# 03_-LED7SEG.net
KiCad netlist of a schematic drawn in Altium Designer
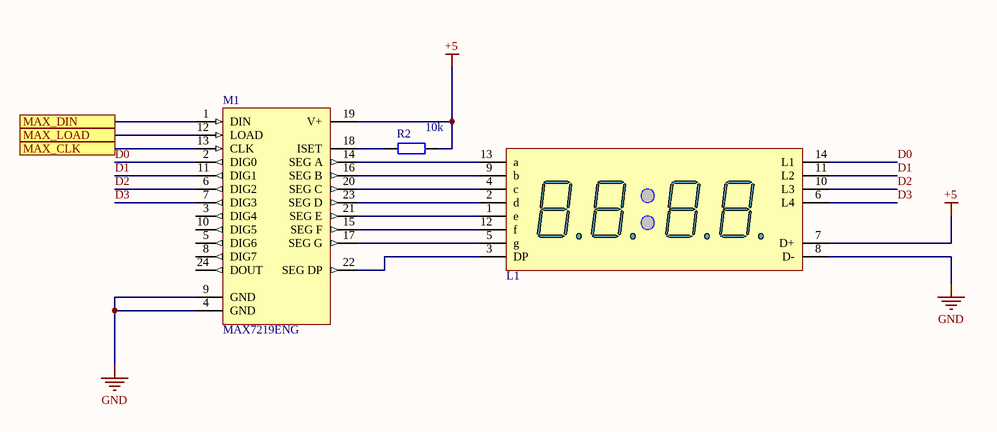
[diagram p0: [03]-LED7SEG.SchDoc]

(export (version "E")
  (design (tool "Eeschema 10.0.6"))
  (components
    (comp (ref "L1")
      (value "Led 7 Seg 4 digit - Anode")
      (footprint "LED7SEG-4-0.56-RG")
      (libsource (lib "My Library") (part "LED7SEG-4-RG"))
    )
    (comp (ref "M1")
      (value "MAX7219ENG")
      (footprint "DIP24/W0.3")
      (description "Serially Interfaced, 8-Digit LED Display Driver")
      (fields (field (name "PUBLISHER") "Altium Limited"))
      (libsource (lib "My Library") (part "MAX7219ENG"))
    )
    (comp (ref "R2")
      (value "10k")
      (footprint "RES_SMD_0805")
      (description "Resistor 1/4W")
      (libsource (lib "My Library") (part "R1/4W"))
    )
  )
  (nets
    (net (code "1") (name "+5") (class "Default")
      (node (ref "L1") (pin "7") (pinfunction "D+_7") (pintype "passive"))
      (node (ref "M1") (pin "19") (pinfunction "V+_19") (pintype "power_in"))
      (node (ref "R2") (pin "2") (pinfunction "2_2") (pintype "passive"))
    )
    (net (code "2") (name "/D0") (class "Default")
      (node (ref "L1") (pin "14") (pinfunction "L1_14") (pintype "passive"))
      (node (ref "M1") (pin "2") (pinfunction "DIG0_2") (pintype "output"))
    )
    (net (code "3") (name "/D1") (class "Default")
      (node (ref "L1") (pin "11") (pinfunction "L2_11") (pintype "passive"))
      (node (ref "M1") (pin "11") (pinfunction "DIG1_11") (pintype "output"))
    )
    (net (code "4") (name "/D2") (class "Default")
      (node (ref "L1") (pin "10") (pinfunction "L3_10") (pintype "passive"))
      (node (ref "M1") (pin "6") (pinfunction "DIG2_6") (pintype "output"))
    )
    (net (code "5") (name "/D3") (class "Default")
      (node (ref "L1") (pin "6") (pinfunction "L4_6") (pintype "passive"))
      (node (ref "M1") (pin "7") (pinfunction "DIG3_7") (pintype "output"))
    )
    (net (code "6") (name "/MAX_CLK") (class "Default")
      (node (ref "M1") (pin "13") (pinfunction "CLK_13") (pintype "input"))
    )
    (net (code "7") (name "/MAX_DIN") (class "Default")
      (node (ref "M1") (pin "1") (pinfunction "DIN_1") (pintype "input"))
    )
    (net (code "8") (name "/MAX_LOAD") (class "Default")
      (node (ref "M1") (pin "12") (pinfunction "LOAD_12") (pintype "input"))
    )
    (net (code "9") (name "GND") (class "Default")
      (node (ref "L1") (pin "8") (pinfunction "D-_8") (pintype "passive"))
      (node (ref "M1") (pin "4") (pinfunction "GND_4") (pintype "power_in"))
      (node (ref "M1") (pin "9") (pinfunction "GND_9") (pintype "power_in"))
    )
    (net (code "10") (name "Net-(L1-DP)") (class "Default")
      (node (ref "L1") (pin "3") (pinfunction "DP_3") (pintype "passive"))
      (node (ref "M1") (pin "22") (pinfunction "SEG_DP_22") (pintype "output"))
    )
    (net (code "11") (name "Net-(L1-a)") (class "Default")
      (node (ref "L1") (pin "13") (pinfunction "a_13") (pintype "passive"))
      (node (ref "M1") (pin "14") (pinfunction "SEG_A_14") (pintype "output"))
    )
    (net (code "12") (name "Net-(L1-b)") (class "Default")
      (node (ref "L1") (pin "9") (pinfunction "b_9") (pintype "passive"))
      (node (ref "M1") (pin "16") (pinfunction "SEG_B_16") (pintype "output"))
    )
    (net (code "13") (name "Net-(L1-c)") (class "Default")
      (node (ref "L1") (pin "4") (pinfunction "c_4") (pintype "passive"))
      (node (ref "M1") (pin "20") (pinfunction "SEG_C_20") (pintype "output"))
    )
    (net (code "14") (name "Net-(L1-d)") (class "Default")
      (node (ref "L1") (pin "2") (pinfunction "d_2") (pintype "passive"))
      (node (ref "M1") (pin "23") (pinfunction "SEG_D_23") (pintype "output"))
    )
    (net (code "15") (name "Net-(L1-e)") (class "Default")
      (node (ref "L1") (pin "1") (pinfunction "e_1") (pintype "passive"))
      (node (ref "M1") (pin "21") (pinfunction "SEG_E_21") (pintype "output"))
    )
    (net (code "16") (name "Net-(L1-f)") (class "Default")
      (node (ref "L1") (pin "12") (pinfunction "f_12") (pintype "passive"))
      (node (ref "M1") (pin "15") (pinfunction "SEG_F_15") (pintype "output"))
    )
    (net (code "17") (name "Net-(L1-g)") (class "Default")
      (node (ref "L1") (pin "5") (pinfunction "g_5") (pintype "passive"))
      (node (ref "M1") (pin "17") (pinfunction "SEG_G_17") (pintype "output"))
    )
    (net (code "18") (name "Net-(M1-ISET)") (class "Default")
      (node (ref "M1") (pin "18") (pinfunction "ISET_18") (pintype "passive"))
      (node (ref "R2") (pin "1") (pinfunction "1_1") (pintype "passive"))
    )
    (net (code "19") (name "unconnected-(M1-DIG4-Pad3)") (class "Default")
      (node (ref "M1") (pin "3") (pinfunction "DIG4_3") (pintype "output"))
    )
    (net (code "20") (name "unconnected-(M1-DIG5-Pad10)") (class "Default")
      (node (ref "M1") (pin "10") (pinfunction "DIG5_10") (pintype "output"))
    )
    (net (code "21") (name "unconnected-(M1-DIG6-Pad5)") (class "Default")
      (node (ref "M1") (pin "5") (pinfunction "DIG6_5") (pintype "output"))
    )
    (net (code "22") (name "unconnected-(M1-DIG7-Pad8)") (class "Default")
      (node (ref "M1") (pin "8") (pinfunction "DIG7_8") (pintype "output"))
    )
    (net (code "23") (name "unconnected-(M1-DOUT-Pad24)") (class "Default")
      (node (ref "M1") (pin "24") (pinfunction "DOUT_24") (pintype "output"))
    )
  )
)
